# Current_Source.net
KiCad netlist of a schematic drawn in Altium Designer
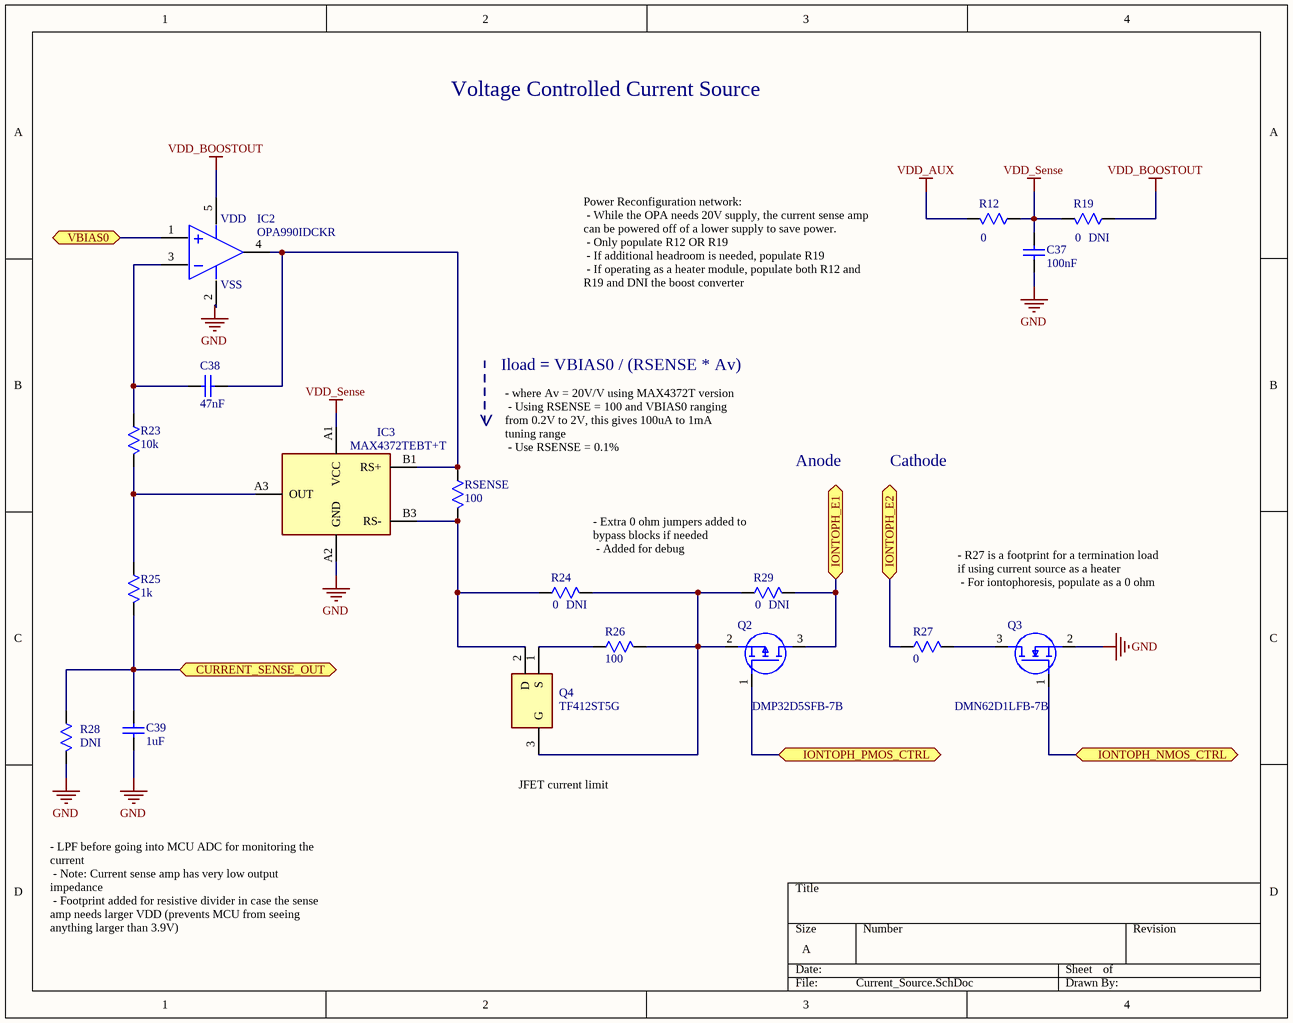
[diagram p0: Current_Source.SchDoc]

(export (version "E")
  (design (tool "Eeschema 10.0.6"))
  (components
    (comp (ref "C37")
      (value "100nF")
      (footprint "0201 cap")
      (description "Multilayer Chip Capacitor")
      (fields (field (name "Comment") "CAP") (field (name "DESIGNER") "OMIGA"))
      (libsource (lib "Schlib") (part "CAP SMD"))
    )
    (comp (ref "C38")
      (value "47nF")
      (footprint "0201 cap")
      (description "Multilayer Chip Capacitor")
      (fields (field (name "Comment") "CAP") (field (name "DESIGNER") "OMIGA"))
      (libsource (lib "Schlib") (part "CAP SMD"))
    )
    (comp (ref "C39")
      (value "1uF")
      (footprint "0201 cap")
      (description "Multilayer Chip Capacitor")
      (fields (field (name "Comment") "CAP") (field (name "DESIGNER") "OMIGA"))
      (libsource (lib "Schlib") (part "CAP SMD"))
    )
    (comp (ref "IC2")
      (value "OPA990IDCKR")
      (footprint "SOT65P210X110-5N")
      (description "Integrated Circuit")
      (fields (field (name "MOUSER PART NUMBER") "595-OPA990IDCKR"))
      (libsource (lib "Schlib") (part "OPA990IDCKR"))
    )
    (comp (ref "IC3")
      (value "MAX4372TEBT+T")
      (footprint "BGA5C50P3X2_152X100X67")
      (description "Integrated Circuit")
      (fields (field (name "MOUSER PART NUMBER") "700-MAX4372TEBT+T"))
      (libsource (lib "Schlib") (part "MAX4372TEBT+T"))
    )
    (comp (ref "Q2")
      (value "DMP32D5SFB-7B")
      (footprint "DESD6V8DLP7")
      (description "MOSFET (P-Channel)")
      (fields (field (name "MOUSER PART NUMBER") "621-DMP32D5SFB-7B"))
      (libsource (lib "Schlib") (part "DMP32D5SFB-7B"))
    )
    (comp (ref "Q3")
      (value "DMN62D1LFB-7B")
      (footprint "SamacSys:DESD6V8DLP7")
      (description "MOSFET (N-Channel)")
      (fields (field (name "MOUSER PART NUMBER") "621-DMN62D1LFB-7B"))
      (libsource (lib "*") (part "DMN62D1LFB-7B"))
    )
    (comp (ref "Q4")
      (value "TF412ST5G")
      (footprint "TF412ST5G")
      (description "N-ch JFET Transistor")
      (fields (field (name "MOUSER PART NUMBER") "863-TF412ST5G"))
      (libsource (lib "Schlib") (part "TF412ST5G"))
    )
    (comp (ref "R12")
      (value "0")
      (footprint "0201 res")
      (description "Surface Mount Resistor")
      (fields (field (name "Comment") "RES") (field (name "DESIGNER") "OMIGA"))
      (libsource (lib "Schlib") (part "RES SMD"))
    )
    (comp (ref "R19")
      (value "0")
      (footprint "0201 res")
      (description "Surface Mount Resistor")
      (fields
        (field (name "DO NOT INSTALL") "DNI")
        (field (name "Comment") "RES")
        (field (name "DESIGNER") "OMIGA")
      )
      (libsource (lib "Schlib") (part "RES SMD"))
    )
    (comp (ref "R23")
      (value "10k")
      (footprint "0201 res")
      (description "Surface Mount Resistor")
      (fields (field (name "Comment") "RES") (field (name "DESIGNER") "OMIGA"))
      (libsource (lib "Schlib") (part "RES SMD"))
    )
    (comp (ref "R24")
      (value "0")
      (footprint "0201 res")
      (description "Surface Mount Resistor")
      (fields
        (field (name "DO NOT INSTALL") "DNI")
        (field (name "Comment") "RES")
        (field (name "DESIGNER") "OMIGA")
      )
      (libsource (lib "Schlib") (part "RES SMD"))
    )
    (comp (ref "R25")
      (value "1k")
      (footprint "0201 res")
      (description "Surface Mount Resistor")
      (fields (field (name "Comment") "RES") (field (name "DESIGNER") "OMIGA"))
      (libsource (lib "Schlib") (part "RES SMD"))
    )
    (comp (ref "R26")
      (value "100")
      (footprint "0402-RES")
      (description "Surface Mount Resistor")
      (fields (field (name "Comment") "RES") (field (name "DESIGNER") "OMIGA"))
      (libsource (lib "Schlib") (part "RES SMD"))
    )
    (comp (ref "R27")
      (value "0")
      (footprint "0201 res")
      (description "Surface Mount Resistor")
      (fields (field (name "Comment") "RES") (field (name "DESIGNER") "OMIGA"))
      (libsource (lib "Schlib") (part "RES SMD"))
    )
    (comp (ref "R28")
      (value "RES")
      (footprint "0201 res")
      (description "Surface Mount Resistor")
      (fields (field (name "DO NOT INSTALL") "DNI") (field (name "DESIGNER") "OMIGA"))
      (libsource (lib "Schlib") (part "RES SMD"))
    )
    (comp (ref "R29")
      (value "0")
      (footprint "0201 res")
      (description "Surface Mount Resistor")
      (fields
        (field (name "DO NOT INSTALL") "DNI")
        (field (name "Comment") "RES")
        (field (name "DESIGNER") "OMIGA")
      )
      (libsource (lib "Schlib") (part "RES SMD"))
    )
    (comp (ref "RSENSE")
      (value "100")
      (footprint "0402-RES")
      (description "Surface Mount Resistor")
      (fields (field (name "Comment") "RES") (field (name "DESIGNER") "OMIGA"))
      (libsource (lib "Schlib") (part "RES SMD"))
    )
  )
  (nets
    (net (code "1") (name "/CURRENT_SENSE_OUT") (class "Default")
      (node (ref "C39") (pin "2") (pinfunction "2_2") (pintype "passive"))
      (node (ref "R25") (pin "2") (pinfunction "2_2") (pintype "passive"))
      (node (ref "R28") (pin "1") (pinfunction "1_1") (pintype "passive"))
    )
    (net (code "2") (name "/IONTOPH_E1") (class "Default")
      (node (ref "Q2") (pin "3") (pinfunction "D_3") (pintype "passive"))
      (node (ref "R29") (pin "1") (pinfunction "1_1") (pintype "passive"))
    )
    (net (code "3") (name "/IONTOPH_E2") (class "Default")
      (node (ref "R27") (pin "1") (pinfunction "1_1") (pintype "passive"))
    )
    (net (code "4") (name "/IONTOPH_NMOS_CTRL") (class "Default")
      (node (ref "Q3") (pin "1") (pinfunction "G_1") (pintype "passive"))
    )
    (net (code "5") (name "/IONTOPH_PMOS_CTRL") (class "Default")
      (node (ref "Q2") (pin "1") (pinfunction "G_1") (pintype "passive"))
    )
    (net (code "6") (name "/VBIAS0") (class "Default")
      (node (ref "IC2") (pin "1") (pinfunction "IN+_1") (pintype "passive"))
    )
    (net (code "7") (name "GND") (class "Default")
      (node (ref "C37") (pin "1") (pinfunction "1_1") (pintype "passive"))
      (node (ref "C39") (pin "1") (pinfunction "1_1") (pintype "passive"))
      (node (ref "IC2") (pin "2") (pinfunction "V-_2") (pintype "passive"))
      (node (ref "IC3") (pin "A2") (pinfunction "GND_A2") (pintype "passive"))
      (node (ref "Q3") (pin "2") (pinfunction "S_2") (pintype "passive"))
      (node (ref "R28") (pin "2") (pinfunction "2_2") (pintype "passive"))
    )
    (net (code "8") (name "Net-(IC2-IN-)") (class "Default")
      (node (ref "C38") (pin "1") (pinfunction "1_1") (pintype "passive"))
      (node (ref "IC2") (pin "3") (pinfunction "IN-_3") (pintype "passive"))
      (node (ref "R23") (pin "1") (pinfunction "1_1") (pintype "passive"))
    )
    (net (code "9") (name "Net-(IC2-OUT)") (class "Default")
      (node (ref "C38") (pin "2") (pinfunction "2_2") (pintype "passive"))
      (node (ref "IC2") (pin "4") (pinfunction "OUT_4") (pintype "passive"))
      (node (ref "IC3") (pin "B1") (pinfunction "RS+_B1") (pintype "passive"))
      (node (ref "RSENSE") (pin "1") (pinfunction "1_1") (pintype "passive"))
    )
    (net (code "10") (name "Net-(IC3-OUT)") (class "Default")
      (node (ref "IC3") (pin "A3") (pinfunction "OUT_A3") (pintype "passive"))
      (node (ref "R23") (pin "2") (pinfunction "2_2") (pintype "passive"))
      (node (ref "R25") (pin "1") (pinfunction "1_1") (pintype "passive"))
    )
    (net (code "11") (name "Net-(IC3-RS-)") (class "Default")
      (node (ref "IC3") (pin "B3") (pinfunction "RS-_B3") (pintype "passive"))
      (node (ref "Q4") (pin "2") (pinfunction "D_2") (pintype "passive"))
      (node (ref "R24") (pin "2") (pinfunction "2_2") (pintype "passive"))
      (node (ref "RSENSE") (pin "2") (pinfunction "2_2") (pintype "passive"))
    )
    (net (code "12") (name "Net-(Q2-S)") (class "Default")
      (node (ref "Q2") (pin "2") (pinfunction "S_2") (pintype "passive"))
      (node (ref "Q4") (pin "3") (pinfunction "G_3") (pintype "passive"))
      (node (ref "R24") (pin "1") (pinfunction "1_1") (pintype "passive"))
      (node (ref "R26") (pin "2") (pinfunction "2_2") (pintype "passive"))
      (node (ref "R29") (pin "2") (pinfunction "2_2") (pintype "passive"))
    )
    (net (code "13") (name "Net-(Q3-D)") (class "Default")
      (node (ref "Q3") (pin "3") (pinfunction "D_3") (pintype "passive"))
      (node (ref "R27") (pin "2") (pinfunction "2_2") (pintype "passive"))
    )
    (net (code "14") (name "Net-(Q4-S)") (class "Default")
      (node (ref "Q4") (pin "1") (pinfunction "S_1") (pintype "passive"))
      (node (ref "R26") (pin "1") (pinfunction "1_1") (pintype "passive"))
    )
    (net (code "15") (name "VDD_AUX") (class "Default")
      (node (ref "R12") (pin "2") (pinfunction "2_2") (pintype "passive"))
    )
    (net (code "16") (name "VDD_BOOSTOUT") (class "Default")
      (node (ref "IC2") (pin "5") (pinfunction "V+_5") (pintype "passive"))
      (node (ref "R19") (pin "1") (pinfunction "1_1") (pintype "passive"))
    )
    (net (code "17") (name "VDD_Sense") (class "Default")
      (node (ref "C37") (pin "2") (pinfunction "2_2") (pintype "passive"))
      (node (ref "IC3") (pin "A1") (pinfunction "VCC_A1") (pintype "passive"))
      (node (ref "R12") (pin "1") (pinfunction "1_1") (pintype "passive"))
      (node (ref "R19") (pin "2") (pinfunction "2_2") (pintype "passive"))
    )
  )
)
